# Placa_Alimentaci_n_9V.net
KiCad netlist of a schematic drawn in Altium Designer
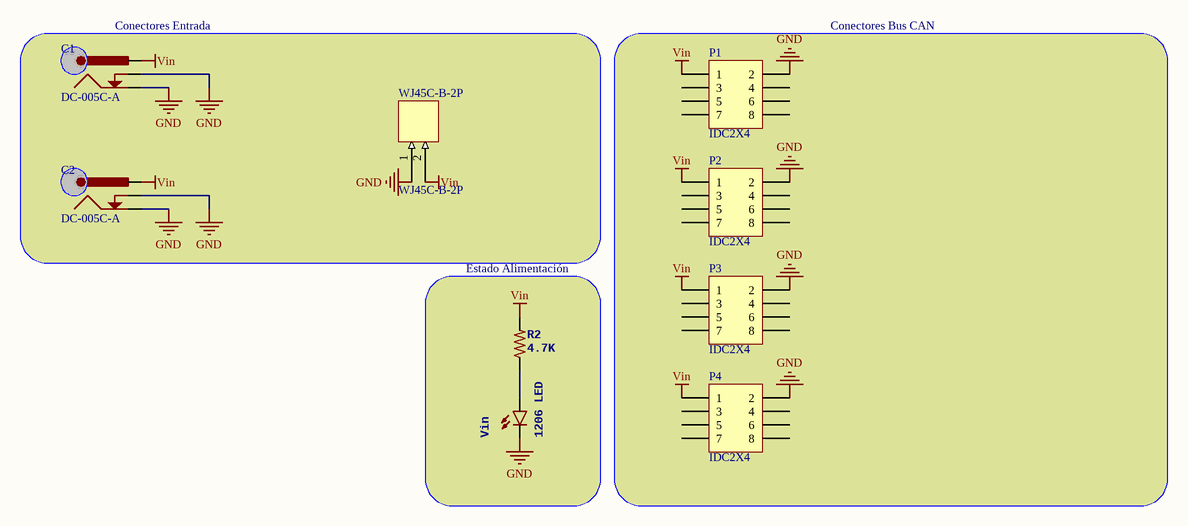
[diagram p0: Placa_Alimentación_9V.SchDoc]

(export (version "E")
  (design (tool "Eeschema 10.0.6"))
  (components
    (comp (ref "C1")
      (value "DC-005C-A")
      (footprint "DC-005C-A")
      (libsource (lib "SparkFun-Connectors") (part "DC-005C-A"))
    )
    (comp (ref "C2")
      (value "DC-005C-A")
      (footprint "DC-005C-A")
      (libsource (lib "SparkFun-Connectors") (part "DC-005C-A"))
    )
    (comp (ref "P1")
      (value "IDC2X4")
      (footprint "IDC2X4")
      (description "Header, 4-Pin, Dual row")
      (fields (field (name "PUBLISHER") "Altium Limited"))
      (libsource (lib "IDC") (part "IDC2X4"))
    )
    (comp (ref "P2")
      (value "IDC2X4")
      (footprint "IDC2X4")
      (description "Header, 4-Pin, Dual row")
      (fields (field (name "PUBLISHER") "Altium Limited"))
      (libsource (lib "IDC") (part "IDC2X4"))
    )
    (comp (ref "P3")
      (value "IDC2X4")
      (footprint "IDC2X4")
      (description "Header, 4-Pin, Dual row")
      (fields (field (name "PUBLISHER") "Altium Limited"))
      (libsource (lib "IDC") (part "IDC2X4"))
    )
    (comp (ref "P4")
      (value "IDC2X4")
      (footprint "IDC2X4")
      (description "Header, 4-Pin, Dual row")
      (fields (field (name "PUBLISHER") "Altium Limited"))
      (libsource (lib "IDC") (part "IDC2X4"))
    )
    (comp (ref "R2")
      (value "4.7K")
      (footprint "SparkFun-Passives:0805")
      (libsource (lib "SparkFun-Passives") (part "RESISTOR0805-RES"))
    )
    (comp (ref "Vin")
      (value "1206 LED")
      (footprint "SparkFun-LED:LED-1206")
      (libsource (lib "SparkFun-LED") (part "LED1206"))
    )
    (comp (ref "WJ45C-B-2P")
      (value "WJ45C-B-2P")
      (footprint "WJ45C-B-2P")
      (libsource (lib "WJ45C") (part "WJ45C-B-2P"))
    )
  )
  (nets
    (net (code "1") (name "GND") (class "Default")
      (node (ref "C1") (pin "2") (pinfunction "SWITCH_2") (pintype "passive"))
      (node (ref "C1") (pin "3") (pinfunction "SHELL_3") (pintype "passive"))
      (node (ref "C2") (pin "2") (pinfunction "SWITCH_2") (pintype "passive"))
      (node (ref "C2") (pin "3") (pinfunction "SHELL_3") (pintype "passive"))
      (node (ref "P1") (pin "2") (pinfunction "2_2") (pintype "passive"))
      (node (ref "P2") (pin "2") (pinfunction "2_2") (pintype "passive"))
      (node (ref "P3") (pin "2") (pinfunction "2_2") (pintype "passive"))
      (node (ref "P4") (pin "2") (pinfunction "2_2") (pintype "passive"))
      (node (ref "Vin") (pin "C") (pinfunction "C_C") (pintype "passive"))
      (node (ref "WJ45C-B-2P") (pin "1") (pintype "input"))
    )
    (net (code "2") (name "Net-(R2-Pad1)") (class "Default")
      (node (ref "R2") (pin "1") (pinfunction "1_1") (pintype "passive"))
      (node (ref "Vin") (pin "A") (pinfunction "A_A") (pintype "passive"))
    )
    (net (code "3") (name "Vin") (class "Default")
      (node (ref "C1") (pin "1") (pinfunction "PIN_1") (pintype "passive"))
      (node (ref "C2") (pin "1") (pinfunction "PIN_1") (pintype "passive"))
      (node (ref "P1") (pin "1") (pinfunction "1_1") (pintype "passive"))
      (node (ref "P2") (pin "1") (pinfunction "1_1") (pintype "passive"))
      (node (ref "P3") (pin "1") (pinfunction "1_1") (pintype "passive"))
      (node (ref "P4") (pin "1") (pinfunction "1_1") (pintype "passive"))
      (node (ref "R2") (pin "2") (pinfunction "2_2") (pintype "passive"))
      (node (ref "WJ45C-B-2P") (pin "2") (pintype "input"))
    )
    (net (code "4") (name "unconnected-(P1-Pad3)") (class "Default")
      (node (ref "P1") (pin "3") (pinfunction "3_3") (pintype "passive"))
    )
    (net (code "5") (name "unconnected-(P1-Pad4)") (class "Default")
      (node (ref "P1") (pin "4") (pinfunction "4_4") (pintype "passive"))
    )
    (net (code "6") (name "unconnected-(P1-Pad5)") (class "Default")
      (node (ref "P1") (pin "5") (pinfunction "5_5") (pintype "passive"))
    )
    (net (code "7") (name "unconnected-(P1-Pad6)") (class "Default")
      (node (ref "P1") (pin "6") (pinfunction "6_6") (pintype "passive"))
    )
    (net (code "8") (name "unconnected-(P1-Pad7)") (class "Default")
      (node (ref "P1") (pin "7") (pinfunction "7_7") (pintype "passive"))
    )
    (net (code "9") (name "unconnected-(P1-Pad8)") (class "Default")
      (node (ref "P1") (pin "8") (pinfunction "8_8") (pintype "passive"))
    )
    (net (code "10") (name "unconnected-(P2-Pad3)") (class "Default")
      (node (ref "P2") (pin "3") (pinfunction "3_3") (pintype "passive"))
    )
    (net (code "11") (name "unconnected-(P2-Pad4)") (class "Default")
      (node (ref "P2") (pin "4") (pinfunction "4_4") (pintype "passive"))
    )
    (net (code "12") (name "unconnected-(P2-Pad5)") (class "Default")
      (node (ref "P2") (pin "5") (pinfunction "5_5") (pintype "passive"))
    )
    (net (code "13") (name "unconnected-(P2-Pad6)") (class "Default")
      (node (ref "P2") (pin "6") (pinfunction "6_6") (pintype "passive"))
    )
    (net (code "14") (name "unconnected-(P2-Pad7)") (class "Default")
      (node (ref "P2") (pin "7") (pinfunction "7_7") (pintype "passive"))
    )
    (net (code "15") (name "unconnected-(P2-Pad8)") (class "Default")
      (node (ref "P2") (pin "8") (pinfunction "8_8") (pintype "passive"))
    )
    (net (code "16") (name "unconnected-(P3-Pad3)") (class "Default")
      (node (ref "P3") (pin "3") (pinfunction "3_3") (pintype "passive"))
    )
    (net (code "17") (name "unconnected-(P3-Pad4)") (class "Default")
      (node (ref "P3") (pin "4") (pinfunction "4_4") (pintype "passive"))
    )
    (net (code "18") (name "unconnected-(P3-Pad5)") (class "Default")
      (node (ref "P3") (pin "5") (pinfunction "5_5") (pintype "passive"))
    )
    (net (code "19") (name "unconnected-(P3-Pad6)") (class "Default")
      (node (ref "P3") (pin "6") (pinfunction "6_6") (pintype "passive"))
    )
    (net (code "20") (name "unconnected-(P3-Pad7)") (class "Default")
      (node (ref "P3") (pin "7") (pinfunction "7_7") (pintype "passive"))
    )
    (net (code "21") (name "unconnected-(P3-Pad8)") (class "Default")
      (node (ref "P3") (pin "8") (pinfunction "8_8") (pintype "passive"))
    )
    (net (code "22") (name "unconnected-(P4-Pad3)") (class "Default")
      (node (ref "P4") (pin "3") (pinfunction "3_3") (pintype "passive"))
    )
    (net (code "23") (name "unconnected-(P4-Pad4)") (class "Default")
      (node (ref "P4") (pin "4") (pinfunction "4_4") (pintype "passive"))
    )
    (net (code "24") (name "unconnected-(P4-Pad5)") (class "Default")
      (node (ref "P4") (pin "5") (pinfunction "5_5") (pintype "passive"))
    )
    (net (code "25") (name "unconnected-(P4-Pad6)") (class "Default")
      (node (ref "P4") (pin "6") (pinfunction "6_6") (pintype "passive"))
    )
    (net (code "26") (name "unconnected-(P4-Pad7)") (class "Default")
      (node (ref "P4") (pin "7") (pinfunction "7_7") (pintype "passive"))
    )
    (net (code "27") (name "unconnected-(P4-Pad8)") (class "Default")
      (node (ref "P4") (pin "8") (pinfunction "8_8") (pintype "passive"))
    )
  )
)
